# Nusbio_TestExtension_01.net
KiCad netlist of a schematic drawn in EAGLE
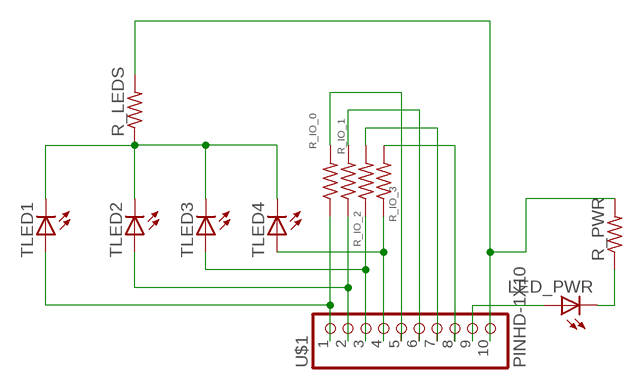
[diagram p0: schematic, sheet 1]

(export (version "E")
  (design (tool "Eeschema 10.0.6"))
  (components
    (comp (ref "LED_PWR")
      (value "LEDSMT1206")
      (footprint "eagle-import:1206")
      (libsource (lib "eagle-import") (part "LEDSMT1206"))
    )
    (comp (ref "R_IO_0")
      (value "R-US_R1206")
      (footprint "eagle-import:R1206")
      (libsource (lib "eagle-import") (part "R-US_R1206"))
    )
    (comp (ref "R_IO_1")
      (value "R-US_R1206")
      (footprint "eagle-import:R1206")
      (libsource (lib "eagle-import") (part "R-US_R1206"))
    )
    (comp (ref "R_IO_2")
      (value "R-US_R1206")
      (footprint "eagle-import:R1206")
      (libsource (lib "eagle-import") (part "R-US_R1206"))
    )
    (comp (ref "R_IO_3")
      (value "R-US_R1206")
      (footprint "eagle-import:R1206")
      (libsource (lib "eagle-import") (part "R-US_R1206"))
    )
    (comp (ref "R_LEDS")
      (value "R-US_R1206")
      (footprint "eagle-import:R1206")
      (libsource (lib "eagle-import") (part "R-US_R1206"))
    )
    (comp (ref "R_PWR")
      (value "R-US_R1206")
      (footprint "eagle-import:R1206")
      (libsource (lib "eagle-import") (part "R-US_R1206"))
    )
    (comp (ref "TLED1")
      (value "LEDSMT1206")
      (footprint "eagle-import:1206")
      (libsource (lib "eagle-import") (part "LEDSMT1206"))
    )
    (comp (ref "TLED2")
      (value "LEDSMT1206")
      (footprint "eagle-import:1206")
      (libsource (lib "eagle-import") (part "LEDSMT1206"))
    )
    (comp (ref "TLED3")
      (value "LEDSMT1206")
      (footprint "eagle-import:1206")
      (libsource (lib "eagle-import") (part "LEDSMT1206"))
    )
    (comp (ref "TLED4")
      (value "LEDSMT1206")
      (footprint "eagle-import:1206")
      (libsource (lib "eagle-import") (part "LEDSMT1206"))
    )
    (comp (ref "U$1")
      (value "PINHD-1X10")
      (footprint "eagle-import:1X10-BIG")
      (libsource (lib "eagle-import") (part "PINHD-1X10"))
    )
  )
  (nets
    (net (code "1") (name "Net-(LED_PWR-PadA)") (class "Default")
      (node (ref "LED_PWR") (pin "A") (pinfunction "A_A") (pintype "passive"))
      (node (ref "U$1") (pin "9") (pinfunction "9_9") (pintype "passive"))
    )
    (net (code "2") (name "Net-(LED_PWR-PadC)") (class "Default")
      (node (ref "LED_PWR") (pin "C") (pinfunction "C_C") (pintype "passive"))
      (node (ref "R_PWR") (pin "1") (pinfunction "1_1") (pintype "passive"))
    )
    (net (code "3") (name "Net-(R_IO_0-Pad1)") (class "Default")
      (node (ref "R_IO_0") (pin "1") (pinfunction "1_1") (pintype "passive"))
      (node (ref "TLED1") (pin "A") (pinfunction "A_A") (pintype "passive"))
      (node (ref "U$1") (pin "1") (pinfunction "1_1") (pintype "passive"))
    )
    (net (code "4") (name "Net-(R_IO_0-Pad2)") (class "Default")
      (node (ref "R_IO_0") (pin "2") (pinfunction "2_2") (pintype "passive"))
      (node (ref "U$1") (pin "5") (pinfunction "5_5") (pintype "passive"))
    )
    (net (code "5") (name "Net-(R_IO_1-Pad1)") (class "Default")
      (node (ref "R_IO_1") (pin "1") (pinfunction "1_1") (pintype "passive"))
      (node (ref "TLED2") (pin "A") (pinfunction "A_A") (pintype "passive"))
      (node (ref "U$1") (pin "2") (pinfunction "2_2") (pintype "passive"))
    )
    (net (code "6") (name "Net-(R_IO_1-Pad2)") (class "Default")
      (node (ref "R_IO_1") (pin "2") (pinfunction "2_2") (pintype "passive"))
      (node (ref "U$1") (pin "6") (pinfunction "6_6") (pintype "passive"))
    )
    (net (code "7") (name "Net-(R_IO_2-Pad1)") (class "Default")
      (node (ref "R_IO_2") (pin "1") (pinfunction "1_1") (pintype "passive"))
      (node (ref "TLED3") (pin "A") (pinfunction "A_A") (pintype "passive"))
      (node (ref "U$1") (pin "3") (pinfunction "3_3") (pintype "passive"))
    )
    (net (code "8") (name "Net-(R_IO_2-Pad2)") (class "Default")
      (node (ref "R_IO_2") (pin "2") (pinfunction "2_2") (pintype "passive"))
      (node (ref "U$1") (pin "7") (pinfunction "7_7") (pintype "passive"))
    )
    (net (code "9") (name "Net-(R_IO_3-Pad1)") (class "Default")
      (node (ref "R_IO_3") (pin "1") (pinfunction "1_1") (pintype "passive"))
      (node (ref "TLED4") (pin "A") (pinfunction "A_A") (pintype "passive"))
      (node (ref "U$1") (pin "4") (pinfunction "4_4") (pintype "passive"))
    )
    (net (code "10") (name "Net-(R_IO_3-Pad2)") (class "Default")
      (node (ref "R_IO_3") (pin "2") (pinfunction "2_2") (pintype "passive"))
      (node (ref "U$1") (pin "8") (pinfunction "8_8") (pintype "passive"))
    )
    (net (code "11") (name "Net-(R_LEDS-Pad1)") (class "Default")
      (node (ref "R_LEDS") (pin "1") (pinfunction "1_1") (pintype "passive"))
      (node (ref "TLED1") (pin "C") (pinfunction "C_C") (pintype "passive"))
      (node (ref "TLED2") (pin "C") (pinfunction "C_C") (pintype "passive"))
      (node (ref "TLED3") (pin "C") (pinfunction "C_C") (pintype "passive"))
      (node (ref "TLED4") (pin "C") (pinfunction "C_C") (pintype "passive"))
    )
    (net (code "12") (name "Net-(R_LEDS-Pad2)") (class "Default")
      (node (ref "R_LEDS") (pin "2") (pinfunction "2_2") (pintype "passive"))
      (node (ref "R_PWR") (pin "2") (pinfunction "2_2") (pintype "passive"))
      (node (ref "U$1") (pin "10") (pinfunction "10_10") (pintype "passive"))
    )
  )
)
